# buttons.net
KiCad netlist of a schematic drawn in EAGLE
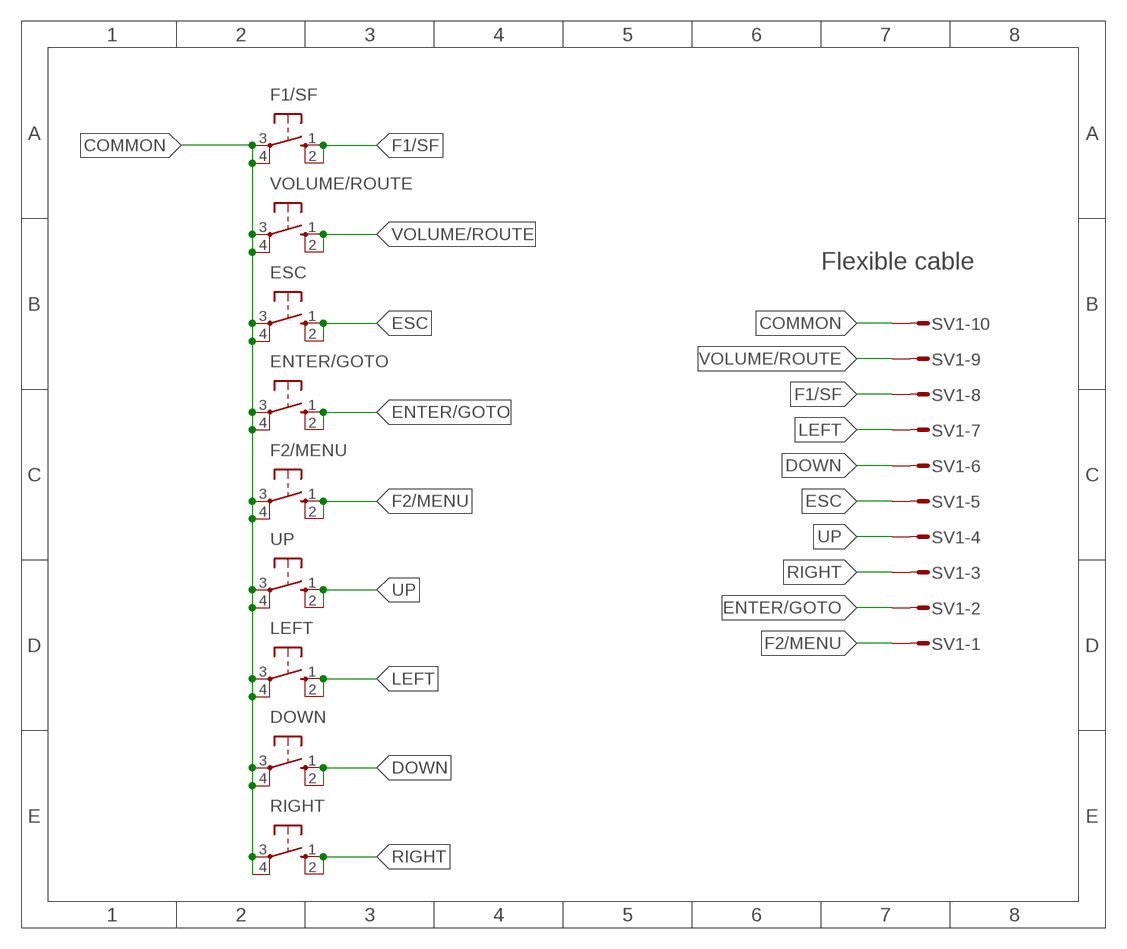
[diagram p0: schematic, sheet 1]

(export (version "E")
  (design (tool "Eeschema 10.0.6"))
  (components
    (comp (ref "DOWN")
      (value "10-XX")
      (footprint "eagle-import:B3F-10XX")
      (fields (field (name "MPN") "B3F-1000"))
      (libsource (lib "eagle-import") (part "10-XX"))
    )
    (comp (ref "ENTER/GOTO")
      (value "10-XX")
      (footprint "eagle-import:B3F-10XX")
      (fields (field (name "MPN") "B3F-1000"))
      (libsource (lib "eagle-import") (part "10-XX"))
    )
    (comp (ref "ESC")
      (value "10-XX")
      (footprint "eagle-import:B3F-10XX")
      (fields (field (name "MPN") "B3F-1000"))
      (libsource (lib "eagle-import") (part "10-XX"))
    )
    (comp (ref "F1/SF")
      (value "10-XX")
      (footprint "eagle-import:B3F-10XX")
      (fields (field (name "MPN") "B3F-1000"))
      (libsource (lib "eagle-import") (part "10-XX"))
    )
    (comp (ref "F2/MENU")
      (value "10-XX")
      (footprint "eagle-import:B3F-10XX")
      (fields (field (name "MPN") "B3F-1000"))
      (libsource (lib "eagle-import") (part "10-XX"))
    )
    (comp (ref "LEFT")
      (value "10-XX")
      (footprint "eagle-import:B3F-10XX")
      (fields (field (name "MPN") "B3F-1000"))
      (libsource (lib "eagle-import") (part "10-XX"))
    )
    (comp (ref "RIGHT")
      (value "10-XX")
      (footprint "eagle-import:B3F-10XX")
      (fields (field (name "MPN") "B3F-1000"))
      (libsource (lib "eagle-import") (part "10-XX"))
    )
    (comp (ref "SV1")
      (value "S10P")
      (footprint "eagle-import:S10P")
      (libsource (lib "eagle-import") (part "S10P"))
    )
    (comp (ref "UP")
      (value "10-XX")
      (footprint "eagle-import:B3F-10XX")
      (fields (field (name "MPN") "B3F-1000"))
      (libsource (lib "eagle-import") (part "10-XX"))
    )
    (comp (ref "VOLUME/ROUTE")
      (value "10-XX")
      (footprint "eagle-import:B3F-10XX")
      (fields (field (name "MPN") "B3F-1000"))
      (libsource (lib "eagle-import") (part "10-XX"))
    )
  )
  (nets
    (net (code "1") (name "COMMON") (class "Default")
      (node (ref "DOWN") (pin "3") (pinfunction "P_3") (pintype "passive"))
      (node (ref "DOWN") (pin "4") (pinfunction "P1_4") (pintype "passive"))
      (node (ref "ENTER/GOTO") (pin "3") (pinfunction "P_3") (pintype "passive"))
      (node (ref "ENTER/GOTO") (pin "4") (pinfunction "P1_4") (pintype "passive"))
      (node (ref "ESC") (pin "3") (pinfunction "P_3") (pintype "passive"))
      (node (ref "ESC") (pin "4") (pinfunction "P1_4") (pintype "passive"))
      (node (ref "F1/SF") (pin "3") (pinfunction "P_3") (pintype "passive"))
      (node (ref "F1/SF") (pin "4") (pinfunction "P1_4") (pintype "passive"))
      (node (ref "F2/MENU") (pin "3") (pinfunction "P_3") (pintype "passive"))
      (node (ref "F2/MENU") (pin "4") (pinfunction "P1_4") (pintype "passive"))
      (node (ref "LEFT") (pin "3") (pinfunction "P_3") (pintype "passive"))
      (node (ref "LEFT") (pin "4") (pinfunction "P1_4") (pintype "passive"))
      (node (ref "RIGHT") (pin "3") (pinfunction "P_3") (pintype "passive"))
      (node (ref "RIGHT") (pin "4") (pinfunction "P1_4") (pintype "passive"))
      (node (ref "SV1") (pin "10") (pinfunction "S_10") (pintype "passive"))
      (node (ref "UP") (pin "3") (pinfunction "P_3") (pintype "passive"))
      (node (ref "UP") (pin "4") (pinfunction "P1_4") (pintype "passive"))
      (node (ref "VOLUME/ROUTE") (pin "3") (pinfunction "P_3") (pintype "passive"))
      (node (ref "VOLUME/ROUTE") (pin "4") (pinfunction "P1_4") (pintype "passive"))
    )
    (net (code "2") (name "DOWN") (class "Default")
      (node (ref "DOWN") (pin "1") (pinfunction "S_1") (pintype "passive"))
      (node (ref "DOWN") (pin "2") (pinfunction "S1_2") (pintype "passive"))
      (node (ref "SV1") (pin "6") (pinfunction "S_6") (pintype "passive"))
    )
    (net (code "3") (name "ENTER{slash}GOTO") (class "Default")
      (node (ref "ENTER/GOTO") (pin "1") (pinfunction "S_1") (pintype "passive"))
      (node (ref "ENTER/GOTO") (pin "2") (pinfunction "S1_2") (pintype "passive"))
      (node (ref "SV1") (pin "2") (pinfunction "S_2") (pintype "passive"))
    )
    (net (code "4") (name "ESC") (class "Default")
      (node (ref "ESC") (pin "1") (pinfunction "S_1") (pintype "passive"))
      (node (ref "ESC") (pin "2") (pinfunction "S1_2") (pintype "passive"))
      (node (ref "SV1") (pin "5") (pinfunction "S_5") (pintype "passive"))
    )
    (net (code "5") (name "F1{slash}SF") (class "Default")
      (node (ref "F1/SF") (pin "1") (pinfunction "S_1") (pintype "passive"))
      (node (ref "F1/SF") (pin "2") (pinfunction "S1_2") (pintype "passive"))
      (node (ref "SV1") (pin "8") (pinfunction "S_8") (pintype "passive"))
    )
    (net (code "6") (name "F2{slash}MENU") (class "Default")
      (node (ref "F2/MENU") (pin "1") (pinfunction "S_1") (pintype "passive"))
      (node (ref "F2/MENU") (pin "2") (pinfunction "S1_2") (pintype "passive"))
      (node (ref "SV1") (pin "1") (pinfunction "S_1") (pintype "passive"))
    )
    (net (code "7") (name "LEFT") (class "Default")
      (node (ref "LEFT") (pin "1") (pinfunction "S_1") (pintype "passive"))
      (node (ref "LEFT") (pin "2") (pinfunction "S1_2") (pintype "passive"))
      (node (ref "SV1") (pin "7") (pinfunction "S_7") (pintype "passive"))
    )
    (net (code "8") (name "RIGHT") (class "Default")
      (node (ref "RIGHT") (pin "1") (pinfunction "S_1") (pintype "passive"))
      (node (ref "RIGHT") (pin "2") (pinfunction "S1_2") (pintype "passive"))
      (node (ref "SV1") (pin "3") (pinfunction "S_3") (pintype "passive"))
    )
    (net (code "9") (name "UP") (class "Default")
      (node (ref "SV1") (pin "4") (pinfunction "S_4") (pintype "passive"))
      (node (ref "UP") (pin "1") (pinfunction "S_1") (pintype "passive"))
      (node (ref "UP") (pin "2") (pinfunction "S1_2") (pintype "passive"))
    )
    (net (code "10") (name "VOLUME{slash}ROUTE") (class "Default")
      (node (ref "SV1") (pin "9") (pinfunction "S_9") (pintype "passive"))
      (node (ref "VOLUME/ROUTE") (pin "1") (pinfunction "S_1") (pintype "passive"))
      (node (ref "VOLUME/ROUTE") (pin "2") (pinfunction "S1_2") (pintype "passive"))
    )
  )
)
